# rs485board.net
KiCad netlist of a schematic drawn in EAGLE
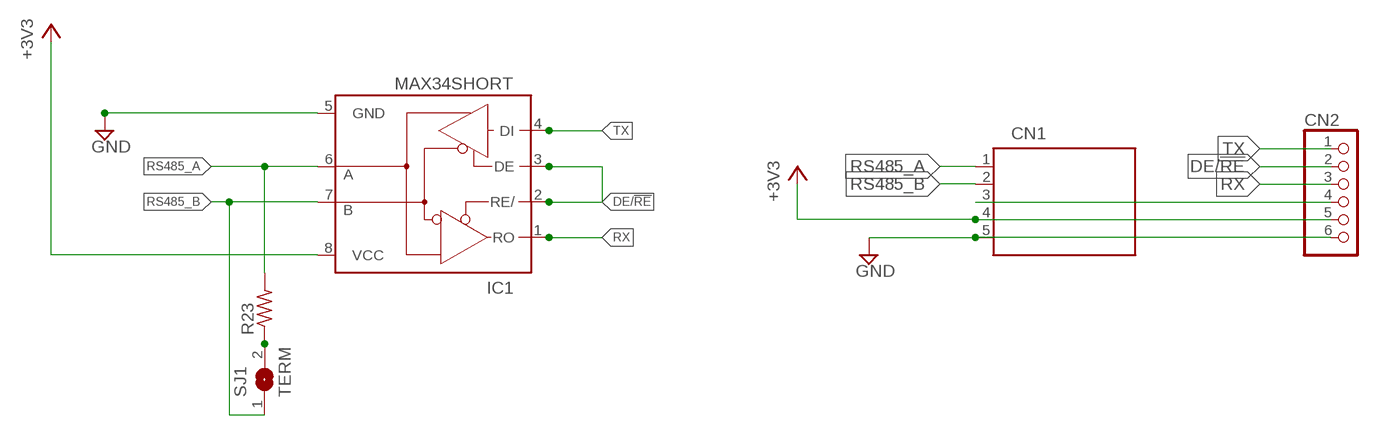
[diagram p0: schematic, sheet 1]

(export (version "E")
  (design (tool "Eeschema 10.0.6"))
  (components
    (comp (ref "CN1")
      (value "5PINZH")
      (footprint "eagle-import:ZH-5")
      (libsource (lib "eagle-import") (part "5PINZH"))
    )
    (comp (ref "CN2")
      (value "PINHD-1X06_2.54")
      (footprint "eagle-import:1X06")
      (libsource (lib "eagle-import") (part "PINHD-1X06_2.54"))
    )
    (comp (ref "IC1")
      (value "MAX34SHORT")
      (footprint "eagle-import:SO08SHORT")
      (libsource (lib "eagle-import") (part "MAX34SHORT"))
    )
    (comp (ref "R23")
      (value "R-US_R0603")
      (footprint "eagle-import:R0603")
      (libsource (lib "eagle-import") (part "R-US_R0603"))
    )
    (comp (ref "SJ1")
      (value "TERM")
      (footprint "eagle-import:SJ")
      (libsource (lib "eagle-import") (part "SJ"))
    )
  )
  (nets
    (net (code "1") (name "+3V3") (class "Default")
      (node (ref "CN1") (pin "4") (pinfunction "4_4") (pintype "passive"))
      (node (ref "CN2") (pin "5") (pinfunction "5_5") (pintype "passive"))
      (node (ref "IC1") (pin "8") (pinfunction "VCC_8") (pintype "power_in"))
    )
    (net (code "2") (name "/DE{slash}~{RE}") (class "Default")
      (node (ref "CN2") (pin "2") (pinfunction "2_2") (pintype "passive"))
      (node (ref "IC1") (pin "2") (pinfunction "RE/_2") (pintype "input"))
      (node (ref "IC1") (pin "3") (pinfunction "DE_3") (pintype "input"))
    )
    (net (code "3") (name "GND") (class "Default")
      (node (ref "CN1") (pin "5") (pinfunction "5_5") (pintype "passive"))
      (node (ref "CN2") (pin "6") (pinfunction "6_6") (pintype "passive"))
      (node (ref "IC1") (pin "5") (pinfunction "GND_5") (pintype "power_in"))
    )
    (net (code "4") (name "Net-(CN1-Pad3)") (class "Default")
      (node (ref "CN1") (pin "3") (pinfunction "3_3") (pintype "passive"))
      (node (ref "CN2") (pin "4") (pinfunction "4_4") (pintype "passive"))
    )
    (net (code "5") (name "Net-(R23-Pad1)") (class "Default")
      (node (ref "R23") (pin "1") (pinfunction "1_1") (pintype "passive"))
      (node (ref "SJ1") (pin "2") (pinfunction "2_2") (pintype "passive"))
    )
    (net (code "6") (name "RS485_A") (class "Default")
      (node (ref "CN1") (pin "1") (pinfunction "1_1") (pintype "passive"))
      (node (ref "IC1") (pin "6") (pinfunction "A_6") (pintype "passive"))
      (node (ref "R23") (pin "2") (pinfunction "2_2") (pintype "passive"))
    )
    (net (code "7") (name "RS485_B") (class "Default")
      (node (ref "CN1") (pin "2") (pinfunction "2_2") (pintype "passive"))
      (node (ref "IC1") (pin "7") (pinfunction "B_7") (pintype "passive"))
      (node (ref "SJ1") (pin "1") (pinfunction "1_1") (pintype "passive"))
    )
    (net (code "8") (name "RX") (class "Default")
      (node (ref "CN2") (pin "3") (pinfunction "3_3") (pintype "passive"))
      (node (ref "IC1") (pin "1") (pinfunction "RO_1") (pintype "output"))
    )
    (net (code "9") (name "TX") (class "Default")
      (node (ref "CN2") (pin "1") (pinfunction "1_1") (pintype "passive"))
      (node (ref "IC1") (pin "4") (pinfunction "DI_4") (pintype "input"))
    )
  )
)
